# Single-ADC_ADS1252U.net
KiCad netlist of a schematic drawn in Altium Designer
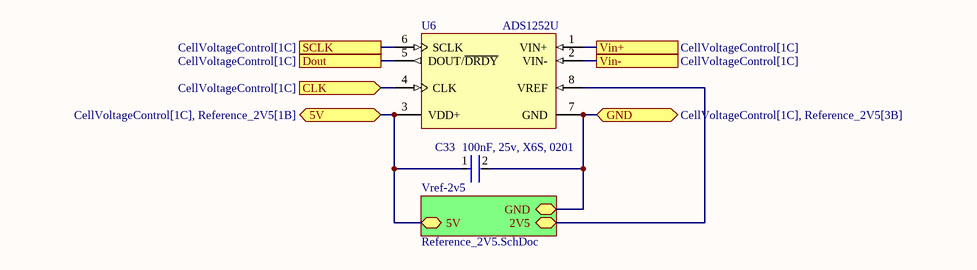
[diagram p0: Single-ADC_ADS1252U.SchDoc]

(export (version "E")
  (design (tool "Eeschema 10.0.6"))
  (components
    (comp (ref "C33")
      (value "100nF, 25v, X6S, 0201")
      (footprint "FP-GRM033-0_03-IPC_B")
      (description "Chip Multilayer Ceramic Capacitors for General Purpose, 0201, 0.10uF, X6S, 22%, 10%, 25V")
      (fields (field (name "TOLERANCE") "10%"))
      (libsource (lib "Altium Content Vault") (part "b4654b650e69147ec39a6b967a45e02"))
    )
    (comp (ref "U6")
      (value "ADS1252U")
      (footprint "TI-D8_M")
      (description "ResolutionPlus 24-Bit, 40 kHz ADC, -40 to 85 degC, 8-pin SOIC (D8), Green (RoHS & no Sb/Br)")
      (fields (field (name "MANUFACTURER") "Texas Instruments"))
      (libsource (lib "Altium Content Vault") (part "TI-ADS125XD8"))
    )
  )
  (nets
    (net (code "1") (name "/2V5") (class "Default")
      (node (ref "U6") (pin "8") (pinfunction "VREF_8") (pintype "input"))
    )
    (net (code "2") (name "/5V") (class "Default")
      (node (ref "C33") (pin "1") (pinfunction "1_1") (pintype "passive"))
      (node (ref "U6") (pin "3") (pinfunction "VDD+_3") (pintype "power_in"))
    )
    (net (code "3") (name "/CLK") (class "Default")
      (node (ref "U6") (pin "4") (pinfunction "CLK_4") (pintype "input"))
    )
    (net (code "4") (name "/Dout") (class "Default")
      (node (ref "U6") (pin "5") (pinfunction "DOUT/~{DRDY}_5") (pintype "output"))
    )
    (net (code "5") (name "/GND") (class "Default")
      (node (ref "C33") (pin "2") (pinfunction "2_2") (pintype "passive"))
      (node (ref "U6") (pin "7") (pinfunction "GND_7") (pintype "power_in"))
    )
    (net (code "6") (name "/SCLK") (class "Default")
      (node (ref "U6") (pin "6") (pinfunction "SCLK_6") (pintype "input"))
    )
    (net (code "7") (name "/Vin+") (class "Default")
      (node (ref "U6") (pin "1") (pinfunction "VIN+_1") (pintype "input"))
    )
    (net (code "8") (name "/Vin-") (class "Default")
      (node (ref "U6") (pin "2") (pinfunction "VIN-_2") (pintype "input"))
    )
  )
)
